# peripheral.net
KiCad netlist of a schematic drawn in EAGLE
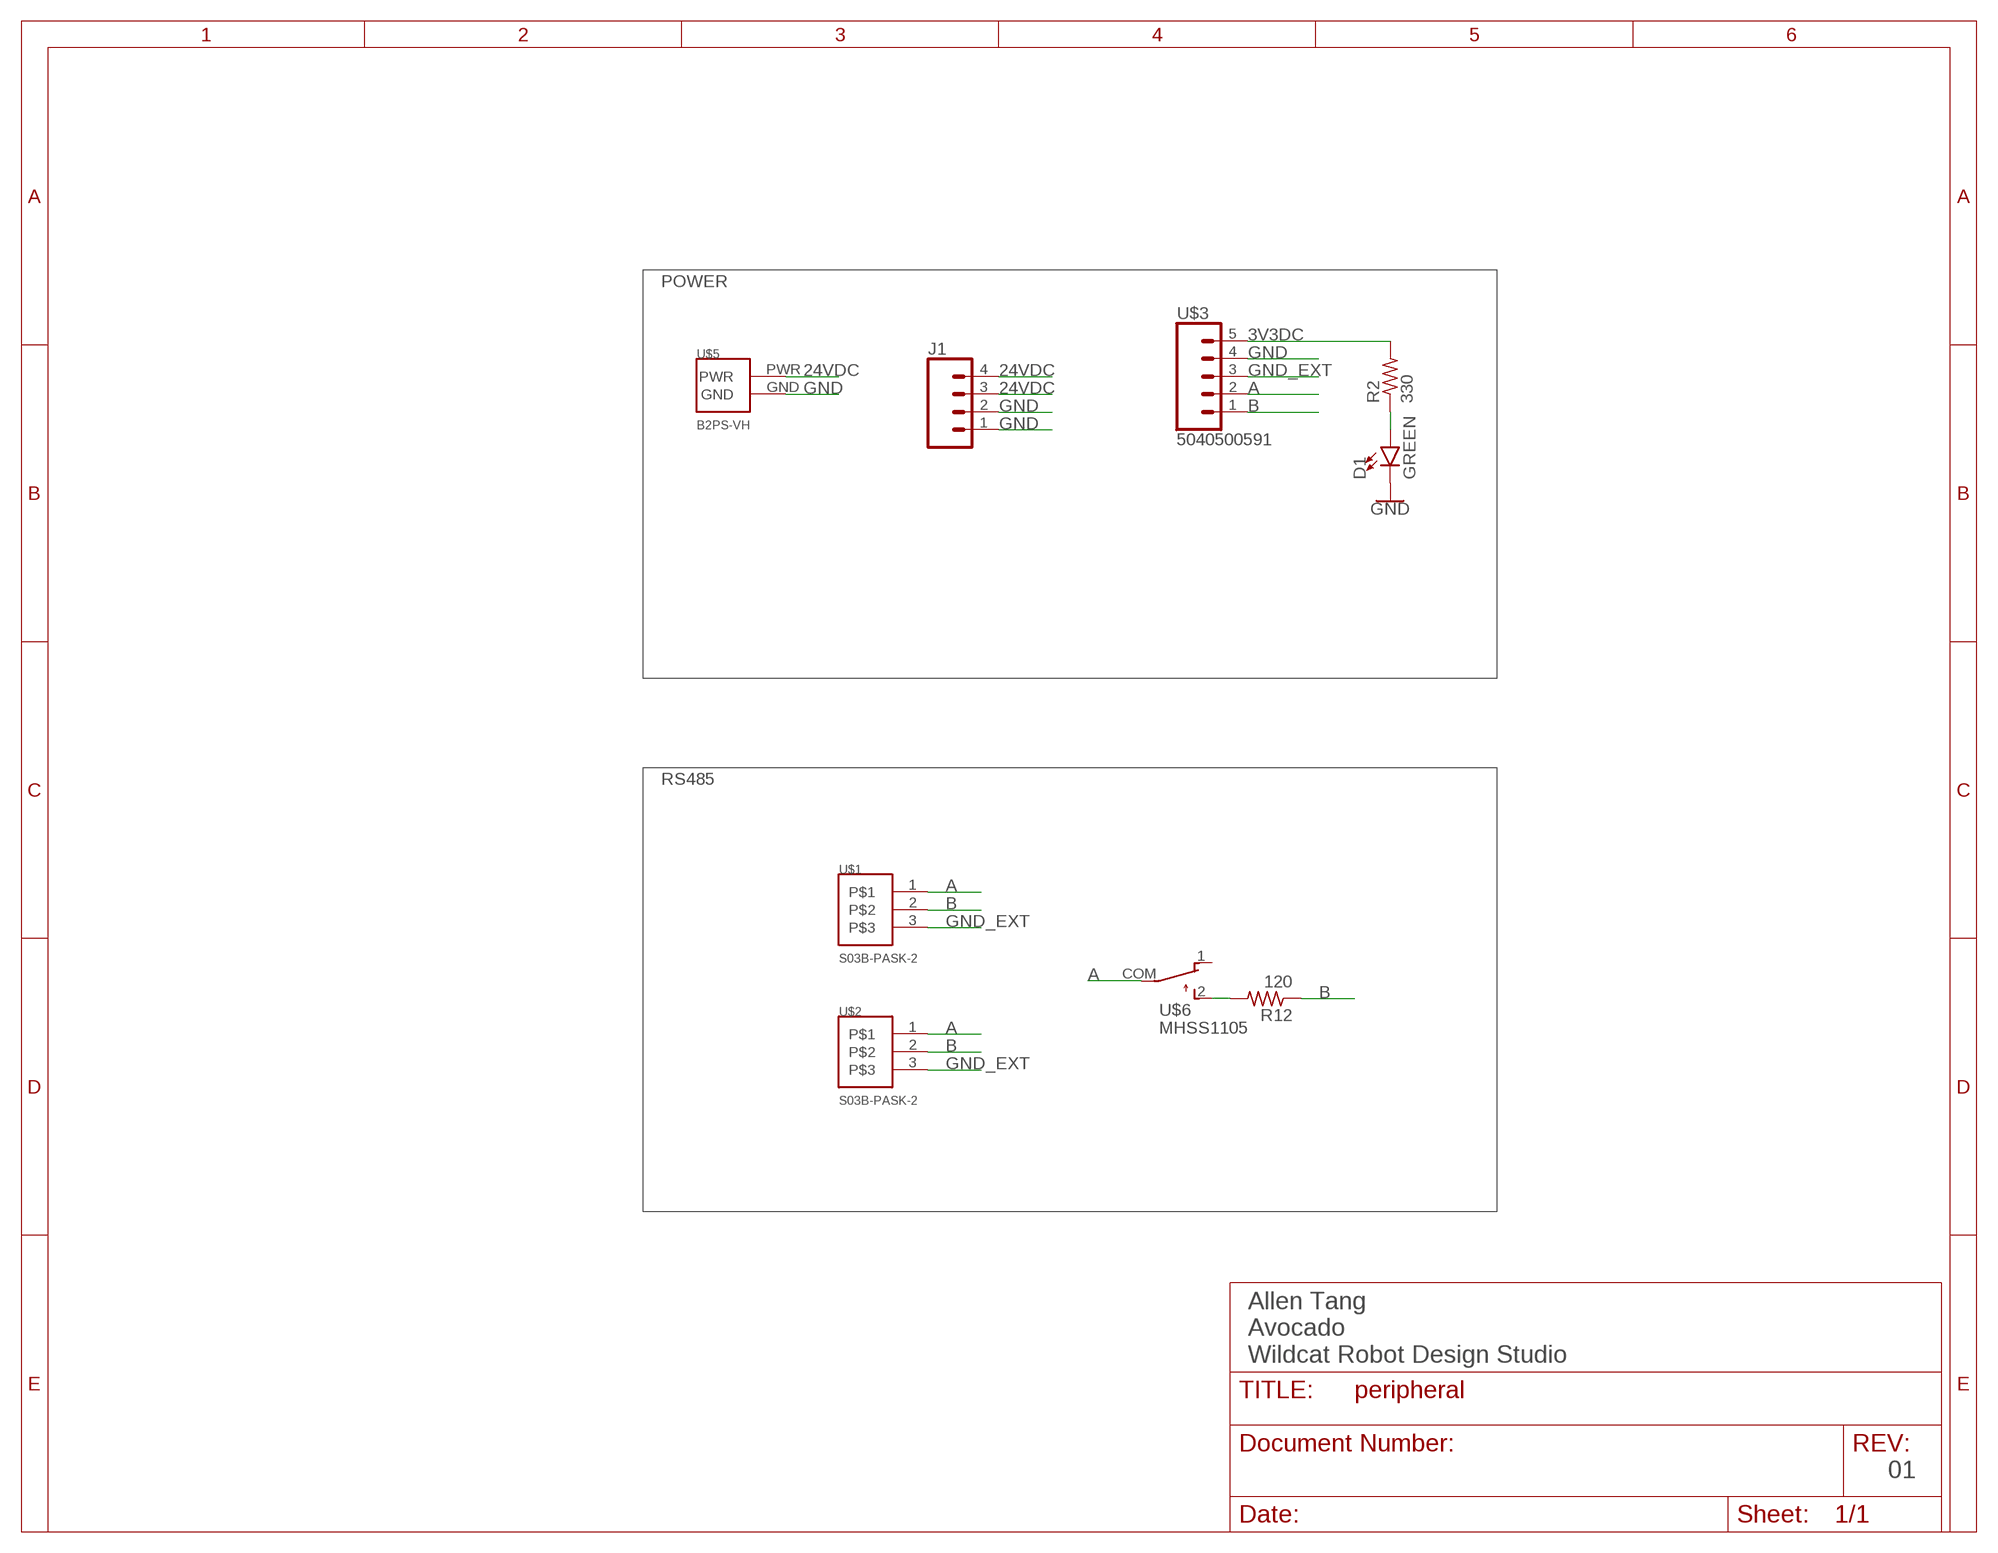
[diagram p0: schematic, sheet 1]

(export (version "E")
  (design (tool "Eeschema 10.0.6"))
  (components
    (comp (ref "D1")
      (value "GREEN")
      (footprint "eagle-import:LED-0603")
      (libsource (lib "eagle-import") (part "LED-GREEN0603"))
    )
    (comp (ref "J1")
      (value "CONN_04")
      (footprint "eagle-import:1X04")
      (libsource (lib "eagle-import") (part "CONN_04"))
    )
    (comp (ref "R2")
      (value "330")
      (footprint "eagle-import:R0805")
      (libsource (lib "eagle-import") (part "R-US_R0805"))
    )
    (comp (ref "R12")
      (value "120")
      (footprint "eagle-import:R0805")
      (libsource (lib "eagle-import") (part "R-US_R0805"))
    )
    (comp (ref "U$1")
      (value "S03B-PASK-2")
      (footprint "eagle-import:S03B-PASK-2")
      (libsource (lib "eagle-import") (part "S03B-PASK-2"))
    )
    (comp (ref "U$2")
      (value "S03B-PASK-2")
      (footprint "eagle-import:S03B-PASK-2")
      (libsource (lib "eagle-import") (part "S03B-PASK-2"))
    )
    (comp (ref "U$3")
      (value "5040500591")
      (footprint "eagle-import:5040500591")
      (libsource (lib "eagle-import") (part "5040500591"))
    )
    (comp (ref "U$5")
      (value "B2PS-VH")
      (footprint "eagle-import:B2PS-VH")
      (libsource (lib "eagle-import") (part "B2PS-VH"))
    )
    (comp (ref "U$6")
      (value "MHSS1105")
      (footprint "eagle-import:MHSS1105")
      (libsource (lib "eagle-import") (part "MHSS1105"))
    )
  )
  (nets
    (net (code "1") (name "/3V3DC") (class "Default")
      (node (ref "R2") (pin "2") (pinfunction "2_2") (pintype "passive"))
      (node (ref "U$3") (pin "5") (pinfunction "5_5") (pintype "passive"))
    )
    (net (code "2") (name "/24VDC") (class "Default")
      (node (ref "J1") (pin "3") (pinfunction "3_3") (pintype "passive"))
      (node (ref "J1") (pin "4") (pinfunction "4_4") (pintype "passive"))
      (node (ref "U$5") (pin "PWR") (pinfunction "PWR_PWR") (pintype "bidirectional"))
    )
    (net (code "3") (name "/A") (class "Default")
      (node (ref "U$1") (pin "1") (pinfunction "P$1_1") (pintype "bidirectional"))
      (node (ref "U$2") (pin "1") (pinfunction "P$1_1") (pintype "bidirectional"))
      (node (ref "U$3") (pin "2") (pinfunction "2_2") (pintype "passive"))
      (node (ref "U$6") (pin "COM") (pinfunction "COM_COM") (pintype "passive"))
    )
    (net (code "4") (name "/B") (class "Default")
      (node (ref "R12") (pin "1") (pinfunction "1_1") (pintype "passive"))
      (node (ref "U$1") (pin "2") (pinfunction "P$2_2") (pintype "bidirectional"))
      (node (ref "U$2") (pin "2") (pinfunction "P$2_2") (pintype "bidirectional"))
      (node (ref "U$3") (pin "1") (pinfunction "1_1") (pintype "passive"))
    )
    (net (code "5") (name "/GND_EXT") (class "Default")
      (node (ref "U$1") (pin "3") (pinfunction "P$3_3") (pintype "bidirectional"))
      (node (ref "U$2") (pin "3") (pinfunction "P$3_3") (pintype "bidirectional"))
      (node (ref "U$3") (pin "3") (pinfunction "3_3") (pintype "passive"))
    )
    (net (code "6") (name "GND") (class "Default")
      (node (ref "D1") (pin "C") (pinfunction "C_C") (pintype "passive"))
      (node (ref "J1") (pin "1") (pinfunction "1_1") (pintype "passive"))
      (node (ref "J1") (pin "2") (pinfunction "2_2") (pintype "passive"))
      (node (ref "U$3") (pin "4") (pinfunction "4_4") (pintype "passive"))
      (node (ref "U$5") (pin "GND") (pinfunction "GND_GND") (pintype "bidirectional"))
    )
    (net (code "7") (name "Net-(D1-PadA)") (class "Default")
      (node (ref "D1") (pin "A") (pinfunction "A_A") (pintype "passive"))
      (node (ref "R2") (pin "1") (pinfunction "1_1") (pintype "passive"))
    )
    (net (code "8") (name "Net-(R12-Pad2)") (class "Default")
      (node (ref "R12") (pin "2") (pinfunction "2_2") (pintype "passive"))
      (node (ref "U$6") (pin "2") (pinfunction "2_2") (pintype "passive"))
    )
    (net (code "9") (name "unconnected-(U$6-Pad1)") (class "Default")
      (node (ref "U$6") (pin "1") (pinfunction "1_1") (pintype "passive"))
    )
  )
)
